# SPD_and_Alert.net
KiCad netlist of a schematic drawn in Altium Designer
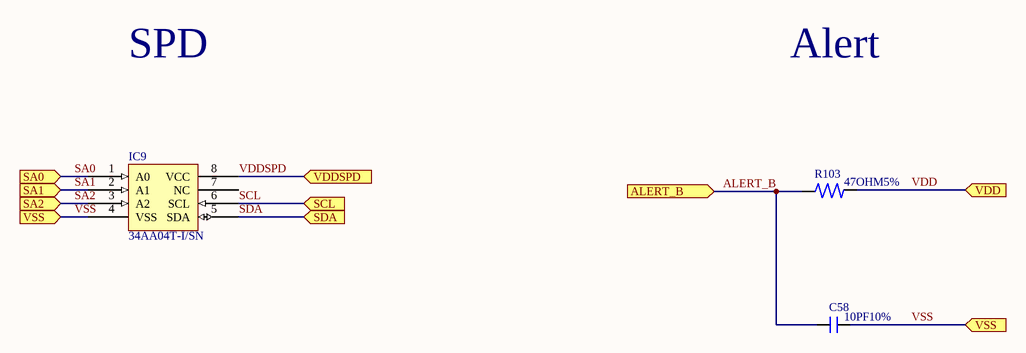
[diagram p0: SPD and Alert.SchDoc]

(export (version "E")
  (design (tool "Eeschema 10.0.6"))
  (components
    (comp (ref "C58")
      (value "Capacitor 0402")
      (footprint "Capacitor 0402")
      (fields
        (field (name "MANUFACTURER") "Vishay")
        (field (name "MANUFACTURER PART NUMBER") "CRCW060310K0FKEA")
        (field (name "TOLERANCE") "1%")
        (field (name "CAPACITANCE") "10PF10%")
      )
      (libsource (lib "RouterIntLib") (part "Capacitor 0201"))
    )
    (comp (ref "IC9")
      (value "34AA04T-I/SN")
      (footprint "34AA04T-I/SN")
      (libsource (lib "RouterIntLib") (part "34AA04T-I/SN"))
    )
    (comp (ref "R103")
      (value "Resistor 0402")
      (footprint "Resistor 0402")
      (fields
        (field (name "MANUFACTURER") "Vishay")
        (field (name "MANUFACTURER PART NUMBER") "CRCW060310K0FKEA")
        (field (name "TOLERANCE") "1%")
        (field (name "RESISTANCE") "47OHM5%")
      )
      (libsource (lib "RouterIntLib") (part "Resistor 0201"))
    )
  )
  (nets
    (net (code "1") (name "/ALERT_B") (class "Default")
      (node (ref "C58") (pin "1") (pinfunction "1_1") (pintype "passive"))
      (node (ref "R103") (pin "1") (pinfunction "1_1") (pintype "passive"))
    )
    (net (code "2") (name "/SA0") (class "Default")
      (node (ref "IC9") (pin "1") (pinfunction "A0_1") (pintype "input"))
    )
    (net (code "3") (name "/SA1") (class "Default")
      (node (ref "IC9") (pin "2") (pinfunction "A1_2") (pintype "input"))
    )
    (net (code "4") (name "/SA2") (class "Default")
      (node (ref "IC9") (pin "3") (pinfunction "A2_3") (pintype "input"))
    )
    (net (code "5") (name "/SCL") (class "Default")
      (node (ref "IC9") (pin "6") (pinfunction "SCL_6") (pintype "input"))
    )
    (net (code "6") (name "/SDA") (class "Default")
      (node (ref "IC9") (pin "5") (pinfunction "SDA_5") (pintype "bidirectional"))
    )
    (net (code "7") (name "/VDD") (class "Default")
      (node (ref "R103") (pin "2") (pinfunction "2_2") (pintype "passive"))
    )
    (net (code "8") (name "/VDDSPD") (class "Default")
      (node (ref "IC9") (pin "8") (pinfunction "VCC_8") (pintype "power_in"))
    )
    (net (code "9") (name "/VSS") (class "Default")
      (node (ref "C58") (pin "2") (pinfunction "2_2") (pintype "passive"))
      (node (ref "IC9") (pin "4") (pinfunction "VSS_4") (pintype "passive"))
    )
    (net (code "10") (name "unconnected-(IC9-NC-Pad7)") (class "Default")
      (node (ref "IC9") (pin "7") (pinfunction "NC_7") (pintype "passive"))
    )
  )
)
